# Fuse_Block.net
KiCad netlist of a schematic drawn in Altium Designer
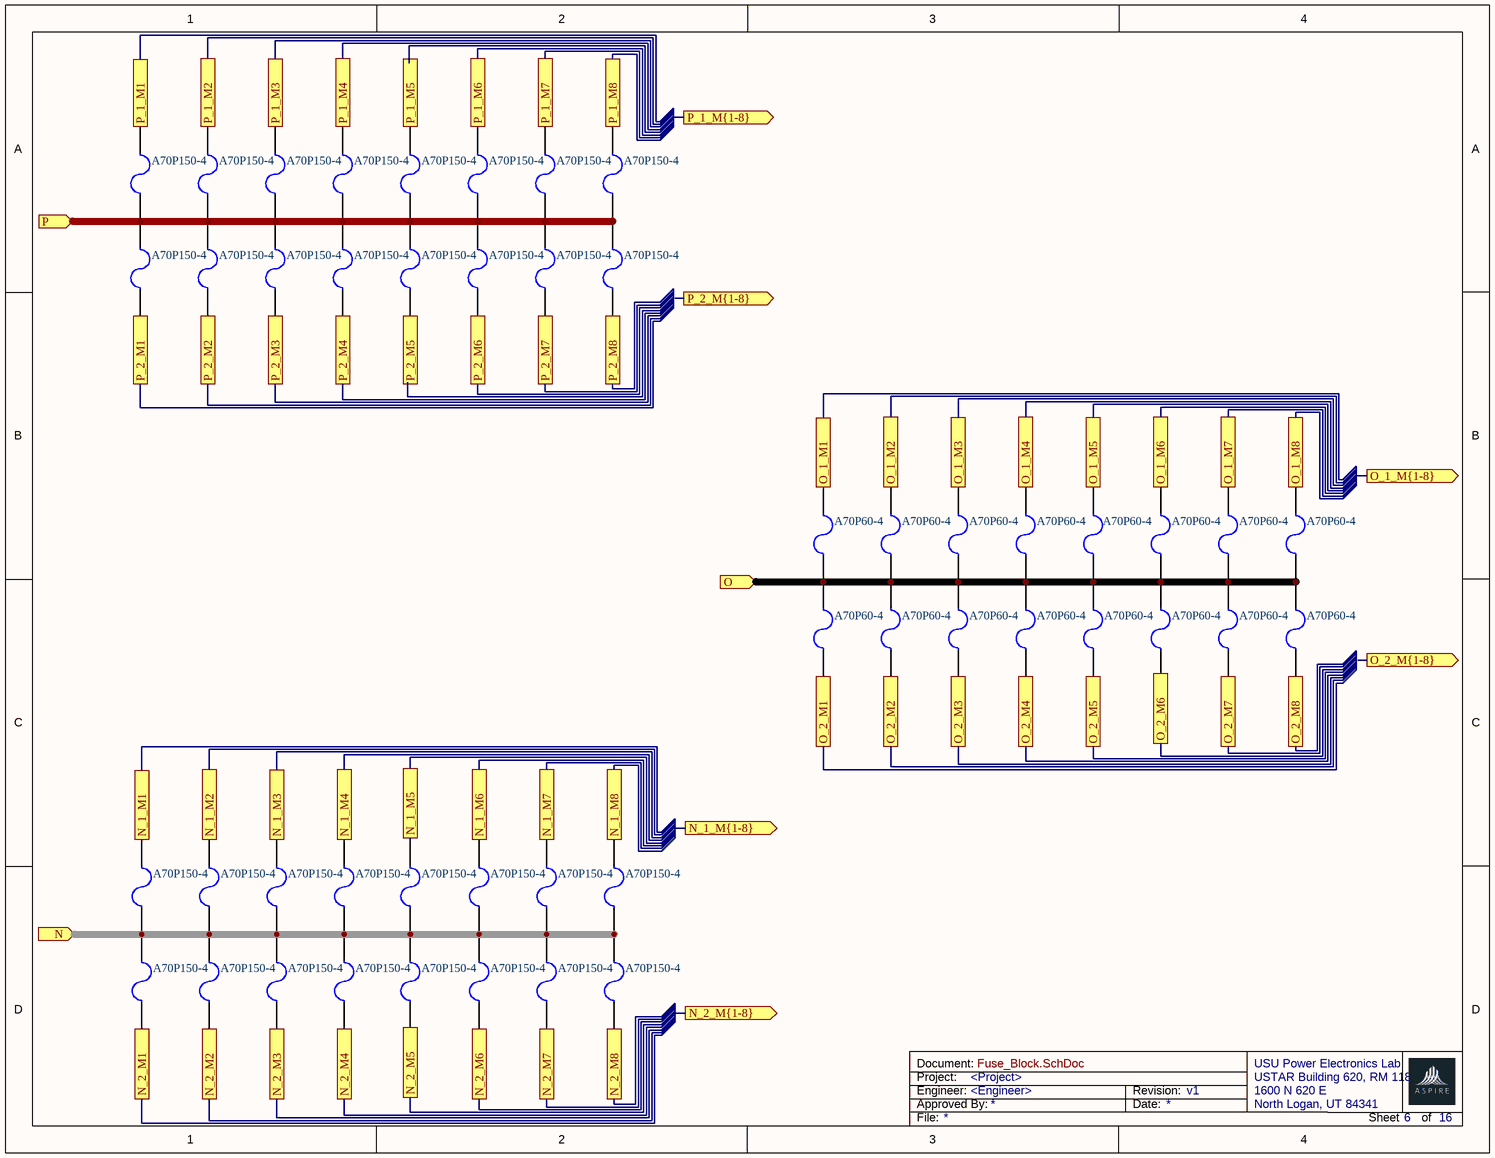
[diagram p0: Fuse_Block.SchDoc]

(export (version "E")
  (design (tool "Eeschema 10.0.6"))
  (components
    (comp (ref "F6")
      (value "A70P150-4")
      (footprint "1206")
      (description "2 A 63 V AC 63 V DC Fuse Board Mount (Cartridge Style Excluded) Surface Mount 1206 (3216 Metric)")
      (fields (field (name "MFR PART #") "0685T2000-01"))
      (libsource (lib "Utah State Power Lab") (part "0685T2000-01"))
    )
    (comp (ref "F17")
      (value "A70P150-4")
      (footprint "1206")
      (description "2 A 63 V AC 63 V DC Fuse Board Mount (Cartridge Style Excluded) Surface Mount 1206 (3216 Metric)")
      (fields (field (name "MFR PART #") "0685T2000-01"))
      (libsource (lib "Utah State Power Lab") (part "0685T2000-01"))
    )
    (comp (ref "F18")
      (value "A70P150-4")
      (footprint "1206")
      (description "2 A 63 V AC 63 V DC Fuse Board Mount (Cartridge Style Excluded) Surface Mount 1206 (3216 Metric)")
      (fields (field (name "MFR PART #") "0685T2000-01"))
      (libsource (lib "Utah State Power Lab") (part "0685T2000-01"))
    )
    (comp (ref "F19")
      (value "A70P150-4")
      (footprint "1206")
      (description "2 A 63 V AC 63 V DC Fuse Board Mount (Cartridge Style Excluded) Surface Mount 1206 (3216 Metric)")
      (fields (field (name "MFR PART #") "0685T2000-01"))
      (libsource (lib "Utah State Power Lab") (part "0685T2000-01"))
    )
    (comp (ref "F20")
      (value "A70P150-4")
      (footprint "1206")
      (description "2 A 63 V AC 63 V DC Fuse Board Mount (Cartridge Style Excluded) Surface Mount 1206 (3216 Metric)")
      (fields (field (name "MFR PART #") "0685T2000-01"))
      (libsource (lib "Utah State Power Lab") (part "0685T2000-01"))
    )
    (comp (ref "F21")
      (value "A70P150-4")
      (footprint "1206")
      (description "2 A 63 V AC 63 V DC Fuse Board Mount (Cartridge Style Excluded) Surface Mount 1206 (3216 Metric)")
      (fields (field (name "MFR PART #") "0685T2000-01"))
      (libsource (lib "Utah State Power Lab") (part "0685T2000-01"))
    )
    (comp (ref "F22")
      (value "A70P150-4")
      (footprint "1206")
      (description "2 A 63 V AC 63 V DC Fuse Board Mount (Cartridge Style Excluded) Surface Mount 1206 (3216 Metric)")
      (fields (field (name "MFR PART #") "0685T2000-01"))
      (libsource (lib "Utah State Power Lab") (part "0685T2000-01"))
    )
    (comp (ref "F23")
      (value "A70P150-4")
      (footprint "1206")
      (description "2 A 63 V AC 63 V DC Fuse Board Mount (Cartridge Style Excluded) Surface Mount 1206 (3216 Metric)")
      (fields (field (name "MFR PART #") "0685T2000-01"))
      (libsource (lib "Utah State Power Lab") (part "0685T2000-01"))
    )
    (comp (ref "F24")
      (value "A70P150-4")
      (footprint "1206")
      (description "2 A 63 V AC 63 V DC Fuse Board Mount (Cartridge Style Excluded) Surface Mount 1206 (3216 Metric)")
      (fields (field (name "MFR PART #") "0685T2000-01"))
      (libsource (lib "Utah State Power Lab") (part "0685T2000-01"))
    )
    (comp (ref "F25")
      (value "A70P150-4")
      (footprint "1206")
      (description "2 A 63 V AC 63 V DC Fuse Board Mount (Cartridge Style Excluded) Surface Mount 1206 (3216 Metric)")
      (fields (field (name "MFR PART #") "0685T2000-01"))
      (libsource (lib "Utah State Power Lab") (part "0685T2000-01"))
    )
    (comp (ref "F26")
      (value "A70P150-4")
      (footprint "1206")
      (description "2 A 63 V AC 63 V DC Fuse Board Mount (Cartridge Style Excluded) Surface Mount 1206 (3216 Metric)")
      (fields (field (name "MFR PART #") "0685T2000-01"))
      (libsource (lib "Utah State Power Lab") (part "0685T2000-01"))
    )
    (comp (ref "F27")
      (value "A70P150-4")
      (footprint "1206")
      (description "2 A 63 V AC 63 V DC Fuse Board Mount (Cartridge Style Excluded) Surface Mount 1206 (3216 Metric)")
      (fields (field (name "MFR PART #") "0685T2000-01"))
      (libsource (lib "Utah State Power Lab") (part "0685T2000-01"))
    )
    (comp (ref "F28")
      (value "A70P150-4")
      (footprint "1206")
      (description "2 A 63 V AC 63 V DC Fuse Board Mount (Cartridge Style Excluded) Surface Mount 1206 (3216 Metric)")
      (fields (field (name "MFR PART #") "0685T2000-01"))
      (libsource (lib "Utah State Power Lab") (part "0685T2000-01"))
    )
    (comp (ref "F29")
      (value "A70P150-4")
      (footprint "1206")
      (description "2 A 63 V AC 63 V DC Fuse Board Mount (Cartridge Style Excluded) Surface Mount 1206 (3216 Metric)")
      (fields (field (name "MFR PART #") "0685T2000-01"))
      (libsource (lib "Utah State Power Lab") (part "0685T2000-01"))
    )
    (comp (ref "F30")
      (value "A70P150-4")
      (footprint "1206")
      (description "2 A 63 V AC 63 V DC Fuse Board Mount (Cartridge Style Excluded) Surface Mount 1206 (3216 Metric)")
      (fields (field (name "MFR PART #") "0685T2000-01"))
      (libsource (lib "Utah State Power Lab") (part "0685T2000-01"))
    )
    (comp (ref "F31")
      (value "A70P150-4")
      (footprint "1206")
      (description "2 A 63 V AC 63 V DC Fuse Board Mount (Cartridge Style Excluded) Surface Mount 1206 (3216 Metric)")
      (fields (field (name "MFR PART #") "0685T2000-01"))
      (libsource (lib "Utah State Power Lab") (part "0685T2000-01"))
    )
    (comp (ref "F32")
      (value "A70P60-4")
      (footprint "1206")
      (description "2 A 63 V AC 63 V DC Fuse Board Mount (Cartridge Style Excluded) Surface Mount 1206 (3216 Metric)")
      (fields (field (name "MFR PART #") "0685T2000-01"))
      (libsource (lib "Utah State Power Lab") (part "0685T2000-01"))
    )
    (comp (ref "F33")
      (value "A70P60-4")
      (footprint "1206")
      (description "2 A 63 V AC 63 V DC Fuse Board Mount (Cartridge Style Excluded) Surface Mount 1206 (3216 Metric)")
      (fields (field (name "MFR PART #") "0685T2000-01"))
      (libsource (lib "Utah State Power Lab") (part "0685T2000-01"))
    )
    (comp (ref "F34")
      (value "A70P60-4")
      (footprint "1206")
      (description "2 A 63 V AC 63 V DC Fuse Board Mount (Cartridge Style Excluded) Surface Mount 1206 (3216 Metric)")
      (fields (field (name "MFR PART #") "0685T2000-01"))
      (libsource (lib "Utah State Power Lab") (part "0685T2000-01"))
    )
    (comp (ref "F35")
      (value "A70P60-4")
      (footprint "1206")
      (description "2 A 63 V AC 63 V DC Fuse Board Mount (Cartridge Style Excluded) Surface Mount 1206 (3216 Metric)")
      (fields (field (name "MFR PART #") "0685T2000-01"))
      (libsource (lib "Utah State Power Lab") (part "0685T2000-01"))
    )
    (comp (ref "F36")
      (value "A70P60-4")
      (footprint "1206")
      (description "2 A 63 V AC 63 V DC Fuse Board Mount (Cartridge Style Excluded) Surface Mount 1206 (3216 Metric)")
      (fields (field (name "MFR PART #") "0685T2000-01"))
      (libsource (lib "Utah State Power Lab") (part "0685T2000-01"))
    )
    (comp (ref "F37")
      (value "A70P60-4")
      (footprint "1206")
      (description "2 A 63 V AC 63 V DC Fuse Board Mount (Cartridge Style Excluded) Surface Mount 1206 (3216 Metric)")
      (fields (field (name "MFR PART #") "0685T2000-01"))
      (libsource (lib "Utah State Power Lab") (part "0685T2000-01"))
    )
    (comp (ref "F38")
      (value "A70P60-4")
      (footprint "1206")
      (description "2 A 63 V AC 63 V DC Fuse Board Mount (Cartridge Style Excluded) Surface Mount 1206 (3216 Metric)")
      (fields (field (name "MFR PART #") "0685T2000-01"))
      (libsource (lib "Utah State Power Lab") (part "0685T2000-01"))
    )
    (comp (ref "F39")
      (value "A70P60-4")
      (footprint "1206")
      (description "2 A 63 V AC 63 V DC Fuse Board Mount (Cartridge Style Excluded) Surface Mount 1206 (3216 Metric)")
      (fields (field (name "MFR PART #") "0685T2000-01"))
      (libsource (lib "Utah State Power Lab") (part "0685T2000-01"))
    )
    (comp (ref "F40")
      (value "A70P60-4")
      (footprint "1206")
      (description "2 A 63 V AC 63 V DC Fuse Board Mount (Cartridge Style Excluded) Surface Mount 1206 (3216 Metric)")
      (fields (field (name "MFR PART #") "0685T2000-01"))
      (libsource (lib "Utah State Power Lab") (part "0685T2000-01"))
    )
    (comp (ref "F41")
      (value "A70P60-4")
      (footprint "1206")
      (description "2 A 63 V AC 63 V DC Fuse Board Mount (Cartridge Style Excluded) Surface Mount 1206 (3216 Metric)")
      (fields (field (name "MFR PART #") "0685T2000-01"))
      (libsource (lib "Utah State Power Lab") (part "0685T2000-01"))
    )
    (comp (ref "F42")
      (value "A70P60-4")
      (footprint "1206")
      (description "2 A 63 V AC 63 V DC Fuse Board Mount (Cartridge Style Excluded) Surface Mount 1206 (3216 Metric)")
      (fields (field (name "MFR PART #") "0685T2000-01"))
      (libsource (lib "Utah State Power Lab") (part "0685T2000-01"))
    )
    (comp (ref "F43")
      (value "A70P60-4")
      (footprint "1206")
      (description "2 A 63 V AC 63 V DC Fuse Board Mount (Cartridge Style Excluded) Surface Mount 1206 (3216 Metric)")
      (fields (field (name "MFR PART #") "0685T2000-01"))
      (libsource (lib "Utah State Power Lab") (part "0685T2000-01"))
    )
    (comp (ref "F44")
      (value "A70P60-4")
      (footprint "1206")
      (description "2 A 63 V AC 63 V DC Fuse Board Mount (Cartridge Style Excluded) Surface Mount 1206 (3216 Metric)")
      (fields (field (name "MFR PART #") "0685T2000-01"))
      (libsource (lib "Utah State Power Lab") (part "0685T2000-01"))
    )
    (comp (ref "F45")
      (value "A70P60-4")
      (footprint "1206")
      (description "2 A 63 V AC 63 V DC Fuse Board Mount (Cartridge Style Excluded) Surface Mount 1206 (3216 Metric)")
      (fields (field (name "MFR PART #") "0685T2000-01"))
      (libsource (lib "Utah State Power Lab") (part "0685T2000-01"))
    )
    (comp (ref "F46")
      (value "A70P60-4")
      (footprint "1206")
      (description "2 A 63 V AC 63 V DC Fuse Board Mount (Cartridge Style Excluded) Surface Mount 1206 (3216 Metric)")
      (fields (field (name "MFR PART #") "0685T2000-01"))
      (libsource (lib "Utah State Power Lab") (part "0685T2000-01"))
    )
    (comp (ref "F47")
      (value "A70P60-4")
      (footprint "1206")
      (description "2 A 63 V AC 63 V DC Fuse Board Mount (Cartridge Style Excluded) Surface Mount 1206 (3216 Metric)")
      (fields (field (name "MFR PART #") "0685T2000-01"))
      (libsource (lib "Utah State Power Lab") (part "0685T2000-01"))
    )
    (comp (ref "F48")
      (value "A70P150-4")
      (footprint "1206")
      (description "2 A 63 V AC 63 V DC Fuse Board Mount (Cartridge Style Excluded) Surface Mount 1206 (3216 Metric)")
      (fields (field (name "MFR PART #") "0685T2000-01"))
      (libsource (lib "Utah State Power Lab") (part "0685T2000-01"))
    )
    (comp (ref "F49")
      (value "A70P150-4")
      (footprint "1206")
      (description "2 A 63 V AC 63 V DC Fuse Board Mount (Cartridge Style Excluded) Surface Mount 1206 (3216 Metric)")
      (fields (field (name "MFR PART #") "0685T2000-01"))
      (libsource (lib "Utah State Power Lab") (part "0685T2000-01"))
    )
    (comp (ref "F50")
      (value "A70P150-4")
      (footprint "1206")
      (description "2 A 63 V AC 63 V DC Fuse Board Mount (Cartridge Style Excluded) Surface Mount 1206 (3216 Metric)")
      (fields (field (name "MFR PART #") "0685T2000-01"))
      (libsource (lib "Utah State Power Lab") (part "0685T2000-01"))
    )
    (comp (ref "F51")
      (value "A70P150-4")
      (footprint "1206")
      (description "2 A 63 V AC 63 V DC Fuse Board Mount (Cartridge Style Excluded) Surface Mount 1206 (3216 Metric)")
      (fields (field (name "MFR PART #") "0685T2000-01"))
      (libsource (lib "Utah State Power Lab") (part "0685T2000-01"))
    )
    (comp (ref "F52")
      (value "A70P150-4")
      (footprint "1206")
      (description "2 A 63 V AC 63 V DC Fuse Board Mount (Cartridge Style Excluded) Surface Mount 1206 (3216 Metric)")
      (fields (field (name "MFR PART #") "0685T2000-01"))
      (libsource (lib "Utah State Power Lab") (part "0685T2000-01"))
    )
    (comp (ref "F53")
      (value "A70P150-4")
      (footprint "1206")
      (description "2 A 63 V AC 63 V DC Fuse Board Mount (Cartridge Style Excluded) Surface Mount 1206 (3216 Metric)")
      (fields (field (name "MFR PART #") "0685T2000-01"))
      (libsource (lib "Utah State Power Lab") (part "0685T2000-01"))
    )
    (comp (ref "F54")
      (value "A70P150-4")
      (footprint "1206")
      (description "2 A 63 V AC 63 V DC Fuse Board Mount (Cartridge Style Excluded) Surface Mount 1206 (3216 Metric)")
      (fields (field (name "MFR PART #") "0685T2000-01"))
      (libsource (lib "Utah State Power Lab") (part "0685T2000-01"))
    )
    (comp (ref "F55")
      (value "A70P150-4")
      (footprint "1206")
      (description "2 A 63 V AC 63 V DC Fuse Board Mount (Cartridge Style Excluded) Surface Mount 1206 (3216 Metric)")
      (fields (field (name "MFR PART #") "0685T2000-01"))
      (libsource (lib "Utah State Power Lab") (part "0685T2000-01"))
    )
    (comp (ref "F56")
      (value "A70P150-4")
      (footprint "1206")
      (description "2 A 63 V AC 63 V DC Fuse Board Mount (Cartridge Style Excluded) Surface Mount 1206 (3216 Metric)")
      (fields (field (name "MFR PART #") "0685T2000-01"))
      (libsource (lib "Utah State Power Lab") (part "0685T2000-01"))
    )
    (comp (ref "F57")
      (value "A70P150-4")
      (footprint "1206")
      (description "2 A 63 V AC 63 V DC Fuse Board Mount (Cartridge Style Excluded) Surface Mount 1206 (3216 Metric)")
      (fields (field (name "MFR PART #") "0685T2000-01"))
      (libsource (lib "Utah State Power Lab") (part "0685T2000-01"))
    )
    (comp (ref "F58")
      (value "A70P150-4")
      (footprint "1206")
      (description "2 A 63 V AC 63 V DC Fuse Board Mount (Cartridge Style Excluded) Surface Mount 1206 (3216 Metric)")
      (fields (field (name "MFR PART #") "0685T2000-01"))
      (libsource (lib "Utah State Power Lab") (part "0685T2000-01"))
    )
    (comp (ref "F59")
      (value "A70P150-4")
      (footprint "1206")
      (description "2 A 63 V AC 63 V DC Fuse Board Mount (Cartridge Style Excluded) Surface Mount 1206 (3216 Metric)")
      (fields (field (name "MFR PART #") "0685T2000-01"))
      (libsource (lib "Utah State Power Lab") (part "0685T2000-01"))
    )
    (comp (ref "F60")
      (value "A70P150-4")
      (footprint "1206")
      (description "2 A 63 V AC 63 V DC Fuse Board Mount (Cartridge Style Excluded) Surface Mount 1206 (3216 Metric)")
      (fields (field (name "MFR PART #") "0685T2000-01"))
      (libsource (lib "Utah State Power Lab") (part "0685T2000-01"))
    )
    (comp (ref "F61")
      (value "A70P150-4")
      (footprint "1206")
      (description "2 A 63 V AC 63 V DC Fuse Board Mount (Cartridge Style Excluded) Surface Mount 1206 (3216 Metric)")
      (fields (field (name "MFR PART #") "0685T2000-01"))
      (libsource (lib "Utah State Power Lab") (part "0685T2000-01"))
    )
    (comp (ref "F62")
      (value "A70P150-4")
      (footprint "1206")
      (description "2 A 63 V AC 63 V DC Fuse Board Mount (Cartridge Style Excluded) Surface Mount 1206 (3216 Metric)")
      (fields (field (name "MFR PART #") "0685T2000-01"))
      (libsource (lib "Utah State Power Lab") (part "0685T2000-01"))
    )
    (comp (ref "F63")
      (value "A70P150-4")
      (footprint "1206")
      (description "2 A 63 V AC 63 V DC Fuse Board Mount (Cartridge Style Excluded) Surface Mount 1206 (3216 Metric)")
      (fields (field (name "MFR PART #") "0685T2000-01"))
      (libsource (lib "Utah State Power Lab") (part "0685T2000-01"))
    )
  )
  (nets
    (net (code "7") (name "/N") (class "Default")
      (node (ref "F48") (pin "1") (pinfunction "1_1") (pintype "passive"))
      (node (ref "F49") (pin "1") (pinfunction "1_1") (pintype "passive"))
      (node (ref "F50") (pin "1") (pinfunction "1_1") (pintype "passive"))
      (node (ref "F51") (pin "1") (pinfunction "1_1") (pintype "passive"))
      (node (ref "F52") (pin "1") (pinfunction "1_1") (pintype "passive"))
      (node (ref "F53") (pin "1") (pinfunction "1_1") (pintype "passive"))
      (node (ref "F54") (pin "1") (pinfunction "1_1") (pintype "passive"))
      (node (ref "F55") (pin "1") (pinfunction "1_1") (pintype "passive"))
      (node (ref "F56") (pin "2") (pinfunction "2_2") (pintype "passive"))
      (node (ref "F57") (pin "2") (pinfunction "2_2") (pintype "passive"))
      (node (ref "F58") (pin "2") (pinfunction "2_2") (pintype "passive"))
      (node (ref "F59") (pin "2") (pinfunction "2_2") (pintype "passive"))
      (node (ref "F60") (pin "2") (pinfunction "2_2") (pintype "passive"))
      (node (ref "F61") (pin "2") (pinfunction "2_2") (pintype "passive"))
      (node (ref "F62") (pin "2") (pinfunction "2_2") (pintype "passive"))
      (node (ref "F63") (pin "2") (pinfunction "2_2") (pintype "passive"))
    )
    (net (code "8") (name "/N_1_M1") (class "Default")
      (node (ref "F48") (pin "2") (pinfunction "2_2") (pintype "passive"))
    )
    (net (code "9") (name "/N_1_M2") (class "Default")
      (node (ref "F49") (pin "2") (pinfunction "2_2") (pintype "passive"))
    )
    (net (code "10") (name "/N_1_M3") (class "Default")
      (node (ref "F50") (pin "2") (pinfunction "2_2") (pintype "passive"))
    )
    (net (code "11") (name "/N_1_M4") (class "Default")
      (node (ref "F51") (pin "2") (pinfunction "2_2") (pintype "passive"))
    )
    (net (code "12") (name "/N_1_M5") (class "Default")
      (node (ref "F52") (pin "2") (pinfunction "2_2") (pintype "passive"))
    )
    (net (code "13") (name "/N_1_M6") (class "Default")
      (node (ref "F53") (pin "2") (pinfunction "2_2") (pintype "passive"))
    )
    (net (code "14") (name "/N_1_M7") (class "Default")
      (node (ref "F54") (pin "2") (pinfunction "2_2") (pintype "passive"))
    )
    (net (code "15") (name "/N_1_M8") (class "Default")
      (node (ref "F55") (pin "2") (pinfunction "2_2") (pintype "passive"))
    )
    (net (code "17") (name "/N_2_M1") (class "Default")
      (node (ref "F56") (pin "1") (pinfunction "1_1") (pintype "passive"))
    )
    (net (code "18") (name "/N_2_M2") (class "Default")
      (node (ref "F57") (pin "1") (pinfunction "1_1") (pintype "passive"))
    )
    (net (code "19") (name "/N_2_M3") (class "Default")
      (node (ref "F58") (pin "1") (pinfunction "1_1") (pintype "passive"))
    )
    (net (code "20") (name "/N_2_M4") (class "Default")
      (node (ref "F59") (pin "1") (pinfunction "1_1") (pintype "passive"))
    )
    (net (code "22") (name "/N_2_M6") (class "Default")
      (node (ref "F61") (pin "1") (pinfunction "1_1") (pintype "passive"))
    )
    (net (code "23") (name "/N_2_M7") (class "Default")
      (node (ref "F62") (pin "1") (pinfunction "1_1") (pintype "passive"))
    )
    (net (code "24") (name "/N_2_M8") (class "Default")
      (node (ref "F63") (pin "1") (pinfunction "1_1") (pintype "passive"))
    )
    (net (code "26") (name "/O") (class "Default")
      (node (ref "F32") (pin "1") (pinfunction "1_1") (pintype "passive"))
      (node (ref "F33") (pin "1") (pinfunction "1_1") (pintype "passive"))
      (node (ref "F34") (pin "1") (pinfunction "1_1") (pintype "passive"))
      (node (ref "F35") (pin "1") (pinfunction "1_1") (pintype "passive"))
      (node (ref "F36") (pin "1") (pinfunction "1_1") (pintype "passive"))
      (node (ref "F37") (pin "1") (pinfunction "1_1") (pintype "passive"))
      (node (ref "F38") (pin "1") (pinfunction "1_1") (pintype "passive"))
      (node (ref "F39") (pin "1") (pinfunction "1_1") (pintype "passive"))
      (node (ref "F40") (pin "2") (pinfunction "2_2") (pintype "passive"))
      (node (ref "F41") (pin "2") (pinfunction "2_2") (pintype "passive"))
      (node (ref "F42") (pin "2") (pinfunction "2_2") (pintype "passive"))
      (node (ref "F43") (pin "2") (pinfunction "2_2") (pintype "passive"))
      (node (ref "F44") (pin "2") (pinfunction "2_2") (pintype "passive"))
      (node (ref "F45") (pin "2") (pinfunction "2_2") (pintype "passive"))
      (node (ref "F46") (pin "2") (pinfunction "2_2") (pintype "passive"))
      (node (ref "F47") (pin "2") (pinfunction "2_2") (pintype "passive"))
    )
    (net (code "27") (name "/O_1_M1") (class "Default")
      (node (ref "F32") (pin "2") (pinfunction "2_2") (pintype "passive"))
    )
    (net (code "28") (name "/O_1_M2") (class "Default")
      (node (ref "F33") (pin "2") (pinfunction "2_2") (pintype "passive"))
    )
    (net (code "29") (name "/O_1_M3") (class "Default")
      (node (ref "F34") (pin "2") (pinfunction "2_2") (pintype "passive"))
    )
    (net (code "30") (name "/O_1_M4") (class "Default")
      (node (ref "F35") (pin "2") (pinfunction "2_2") (pintype "passive"))
    )
    (net (code "31") (name "/O_1_M5") (class "Default")
      (node (ref "F36") (pin "2") (pinfunction "2_2") (pintype "passive"))
    )
    (net (code "32") (name "/O_1_M6") (class "Default")
      (node (ref "F37") (pin "2") (pinfunction "2_2") (pintype "passive"))
    )
    (net (code "33") (name "/O_1_M7") (class "Default")
      (node (ref "F38") (pin "2") (pinfunction "2_2") (pintype "passive"))
    )
    (net (code "34") (name "/O_1_M8") (class "Default")
      (node (ref "F39") (pin "2") (pinfunction "2_2") (pintype "passive"))
    )
    (net (code "36") (name "/O_2_M1") (class "Default")
      (node (ref "F40") (pin "1") (pinfunction "1_1") (pintype "passive"))
    )
    (net (code "37") (name "/O_2_M2") (class "Default")
      (node (ref "F41") (pin "1") (pinfunction "1_1") (pintype "passive"))
    )
    (net (code "38") (name "/O_2_M3") (class "Default")
      (node (ref "F42") (pin "1") (pinfunction "1_1") (pintype "passive"))
    )
    (net (code "39") (name "/O_2_M4") (class "Default")
      (node (ref "F43") (pin "1") (pinfunction "1_1") (pintype "passive"))
    )
    (net (code "40") (name "/O_2_M5") (class "Default")
      (node (ref "F44") (pin "1") (pinfunction "1_1") (pintype "passive"))
    )
    (net (code "42") (name "/O_2_M7") (class "Default")
      (node (ref "F46") (pin "1") (pinfunction "1_1") (pintype "passive"))
    )
    (net (code "43") (name "/O_2_M8") (class "Default")
      (node (ref "F47") (pin "1") (pinfunction "1_1") (pintype "passive"))
    )
    (net (code "45") (name "/P") (class "Default")
      (node (ref "F17") (pin "1") (pinfunction "1_1") (pintype "passive"))
      (node (ref "F18") (pin "1") (pinfunction "1_1") (pintype "passive"))
      (node (ref "F19") (pin "1") (pinfunction "1_1") (pintype "passive"))
      (node (ref "F20") (pin "1") (pinfunction "1_1") (pintype "passive"))
      (node (ref "F21") (pin "1") (pinfunction "1_1") (pintype "passive"))
      (node (ref "F22") (pin "1") (pinfunction "1_1") (pintype "passive"))
      (node (ref "F23") (pin "1") (pinfunction "1_1") (pintype "passive"))
      (node (ref "F24") (pin "2") (pinfunction "2_2") (pintype "passive"))
      (node (ref "F25") (pin "2") (pinfunction "2_2") (pintype "passive"))
      (node (ref "F26") (pin "2") (pinfunction "2_2") (pintype "passive"))
      (node (ref "F27") (pin "2") (pinfunction "2_2") (pintype "passive"))
      (node (ref "F28") (pin "2") (pinfunction "2_2") (pintype "passive"))
      (node (ref "F29") (pin "2") (pinfunction "2_2") (pintype "passive"))
      (node (ref "F30") (pin "2") (pinfunction "2_2") (pintype "passive"))
      (node (ref "F31") (pin "2") (pinfunction "2_2") (pintype "passive"))
      (node (ref "F6") (pin "1") (pinfunction "1_1") (pintype "passive"))
    )
    (net (code "46") (name "/P_1_M1") (class "Default")
      (node (ref "F6") (pin "2") (pinfunction "2_2") (pintype "passive"))
    )
    (net (code "47") (name "/P_1_M2") (class "Default")
      (node (ref "F17") (pin "2") (pinfunction "2_2") (pintype "passive"))
    )
    (net (code "48") (name "/P_1_M3") (class "Default")
      (node (ref "F18") (pin "2") (pinfunction "2_2") (pintype "passive"))
    )
    (net (code "49") (name "/P_1_M4") (class "Default")
      (node (ref "F19") (pin "2") (pinfunction "2_2") (pintype "passive"))
    )
    (net (code "50") (name "/P_1_M5") (class "Default")
      (node (ref "F20") (pin "2") (pinfunction "2_2") (pintype "passive"))
    )
    (net (code "51") (name "/P_1_M6") (class "Default")
      (node (ref "F21") (pin "2") (pinfunction "2_2") (pintype "passive"))
    )
    (net (code "52") (name "/P_1_M7") (class "Default")
      (node (ref "F22") (pin "2") (pinfunction "2_2") (pintype "passive"))
    )
    (net (code "53") (name "/P_1_M8") (class "Default")
      (node (ref "F23") (pin "2") (pinfunction "2_2") (pintype "passive"))
    )
    (net (code "55") (name "/P_2_M1") (class "Default")
      (node (ref "F24") (pin "1") (pinfunction "1_1") (pintype "passive"))
    )
    (net (code "56") (name "/P_2_M2") (class "Default")
      (node (ref "F25") (pin "1") (pinfunction "1_1") (pintype "passive"))
    )
    (net (code "57") (name "/P_2_M3") (class "Default")
      (node (ref "F26") (pin "1") (pinfunction "1_1") (pintype "passive"))
    )
    (net (code "58") (name "/P_2_M4") (class "Default")
      (node (ref "F27") (pin "1") (pinfunction "1_1") (pintype "passive"))
    )
    (net (code "59") (name "/P_2_M5") (class "Default")
      (node (ref "F28") (pin "1") (pinfunction "1_1") (pintype "passive"))
    )
    (net (code "60") (name "/P_2_M6") (class "Default")
      (node (ref "F29") (pin "1") (pinfunction "1_1") (pintype "passive"))
    )
    (net (code "61") (name "/P_2_M7") (class "Default")
      (node (ref "F30") (pin "1") (pinfunction "1_1") (pintype "passive"))
    )
    (net (code "62") (name "/P_2_M8") (class "Default")
      (node (ref "F31") (pin "1") (pinfunction "1_1") (pintype "passive"))
    )
    (net (code "64") (name "unconnected-(F45-Pad1)") (class "Default")
      (node (ref "F45") (pin "1") (pinfunction "1_1") (pintype "passive"))
    )
    (net (code "65") (name "unconnected-(F60-Pad1)") (class "Default")
      (node (ref "F60") (pin "1") (pinfunction "1_1") (pintype "passive"))
    )
  )
)
